# SCH_ADARSH_2025-03-17.net
KiCad netlist of a schematic drawn in EasyEDA
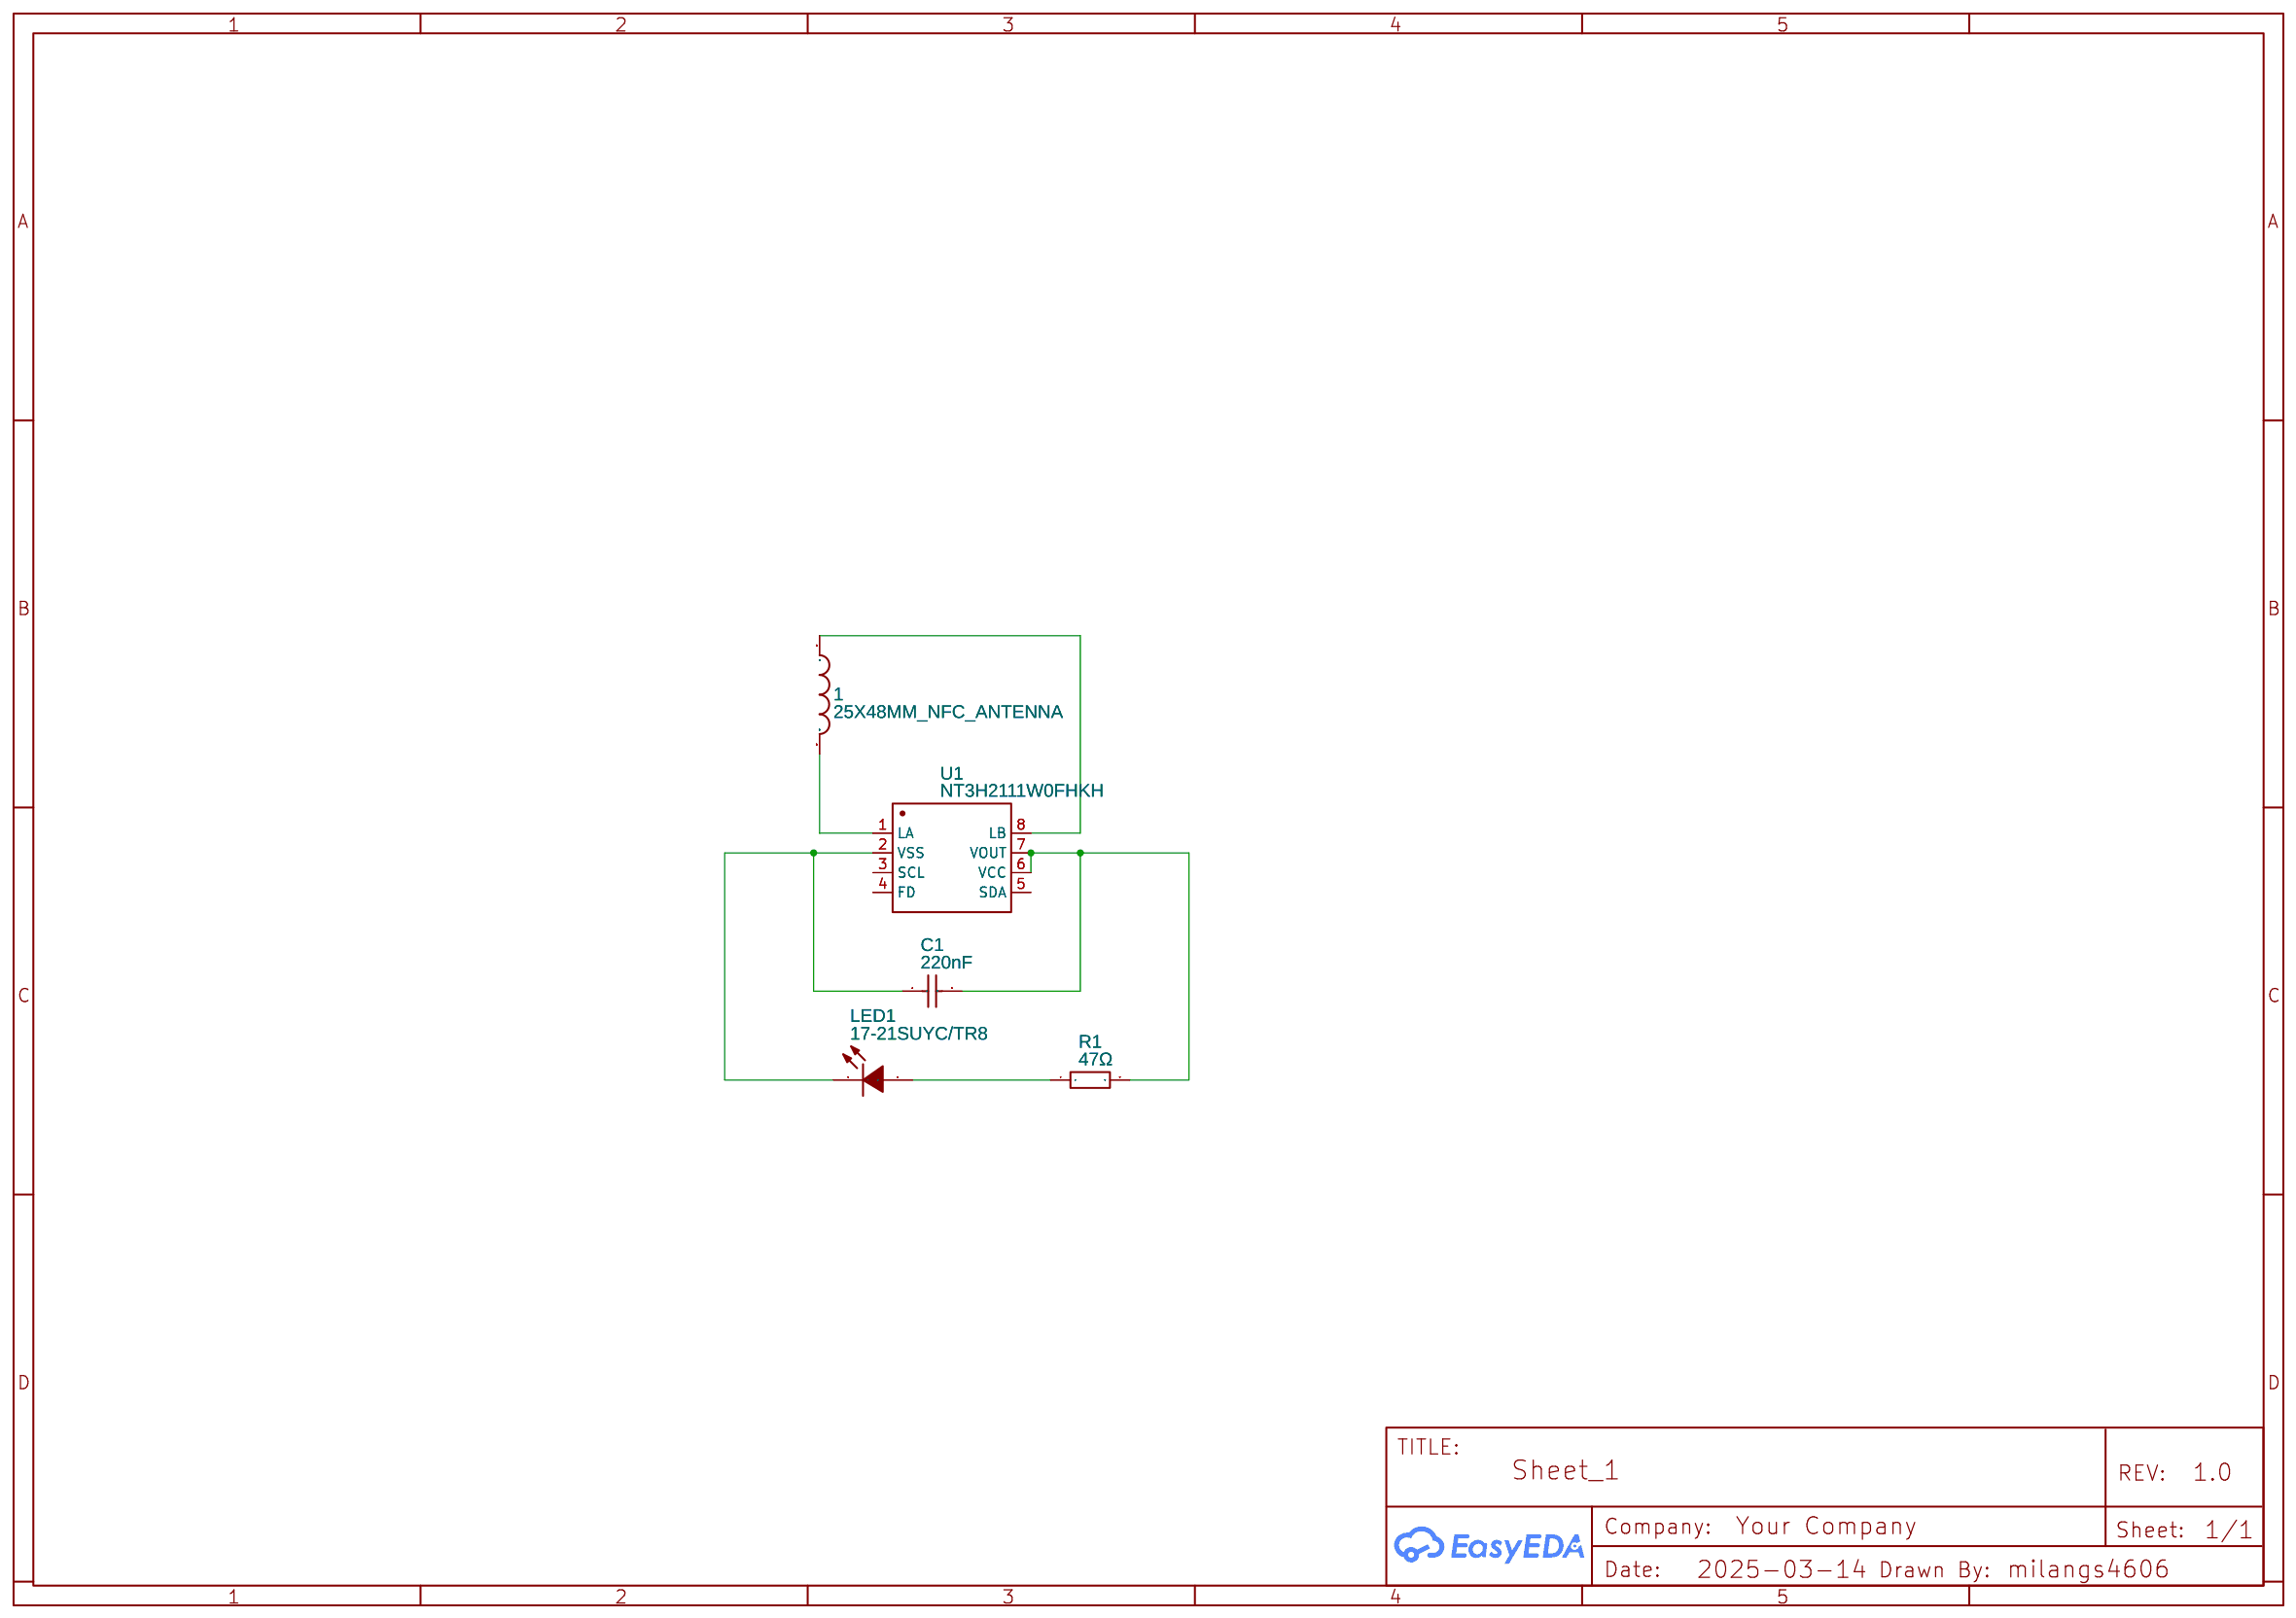
[diagram p0: schematic sheet]

(export (version "E")
  (design (tool "Eeschema 10.0.6"))
  (components
    (comp (ref "1") (value "25X48MM_NFC_ANTENNA") (libsource (lib "") (part "25X48MM_NFC_ANTENNA")))
    (comp (ref "C1")
      (value "220nF")
      (fields
        (field (name "Manufacturer Part") "CL10B224KA8NNNC")
        (field (name "Manufacturer") "SAMSUNG(三星)")
      )
      (libsource (lib "") (part "CL10B224KA8NNNC"))
    )
    (comp (ref "LED1")
      (value "17-21SUYC/TR8")
      (fields (field (name "Manufacturer Part") "KT-0805黄灯") (field (name "Manufacturer") "KENTO"))
      (libsource (lib "") (part "17-21SUYC/TR8"))
    )
    (comp (ref "R1")
      (value "47Ω")
      (fields
        (field (name "Manufacturer Part") "0603WAF470JT5E")
        (field (name "Manufacturer") "UNI-ROYAL(厚声)")
      )
      (libsource (lib "") (part "0603WAF470JT5E"))
    )
    (comp (ref "U1")
      (value "NT3H2111W0FHKH")
      (fields (field (name "Manufacturer") "NXP(恩智浦)"))
      (libsource (lib "") (part "NT3H2111W0FHKH"))
    )
  )
  (nets
    (net (code "1") (name "Net-(LED1-+)") (class "Default")
      (node (ref "LED1") (pin "1") (pinfunction "+_1") (pintype "unspecified"))
      (node (ref "R1") (pin "1") (pinfunction "1_1") (pintype "input"))
    )
    (net (code "2") (name "Net-(LED1--)") (class "Default")
      (node (ref "C1") (pin "1") (pinfunction "1_1") (pintype "input"))
      (node (ref "LED1") (pin "2") (pinfunction "-_2") (pintype "unspecified"))
      (node (ref "U1") (pin "2") (pinfunction "VSS_2") (pintype "unspecified"))
    )
    (net (code "3") (name "Net-(U1-LA)") (class "Default")
      (node (ref "1") (pin "P$2") (pinfunction "P$2_P$2") (pintype "bidirectional"))
      (node (ref "U1") (pin "1") (pinfunction "LA_1") (pintype "unspecified"))
    )
    (net (code "4") (name "Net-(U1-LB)") (class "Default")
      (node (ref "1") (pin "P$1") (pinfunction "P$1_P$1") (pintype "bidirectional"))
      (node (ref "U1") (pin "8") (pinfunction "LB_8") (pintype "unspecified"))
    )
    (net (code "5") (name "Net-(U1-VCC)") (class "Default")
      (node (ref "C1") (pin "2") (pinfunction "2_2") (pintype "input"))
      (node (ref "R1") (pin "2") (pinfunction "2_2") (pintype "input"))
      (node (ref "U1") (pin "6") (pinfunction "VCC_6") (pintype "unspecified"))
      (node (ref "U1") (pin "7") (pinfunction "VOUT_7") (pintype "unspecified"))
    )
    (net (code "6") (name "unconnected-(U1-FD-Pad4)") (class "Default")
      (node (ref "U1") (pin "4") (pinfunction "FD_4") (pintype "unspecified"))
    )
    (net (code "7") (name "unconnected-(U1-SCL-Pad3)") (class "Default")
      (node (ref "U1") (pin "3") (pinfunction "SCL_3") (pintype "unspecified"))
    )
    (net (code "8") (name "unconnected-(U1-SDA-Pad5)") (class "Default")
      (node (ref "U1") (pin "5") (pinfunction "SDA_5") (pintype "unspecified"))
    )
  )
)
